# Psoc-robot.net
KiCad netlist of a schematic drawn in Altium Designer
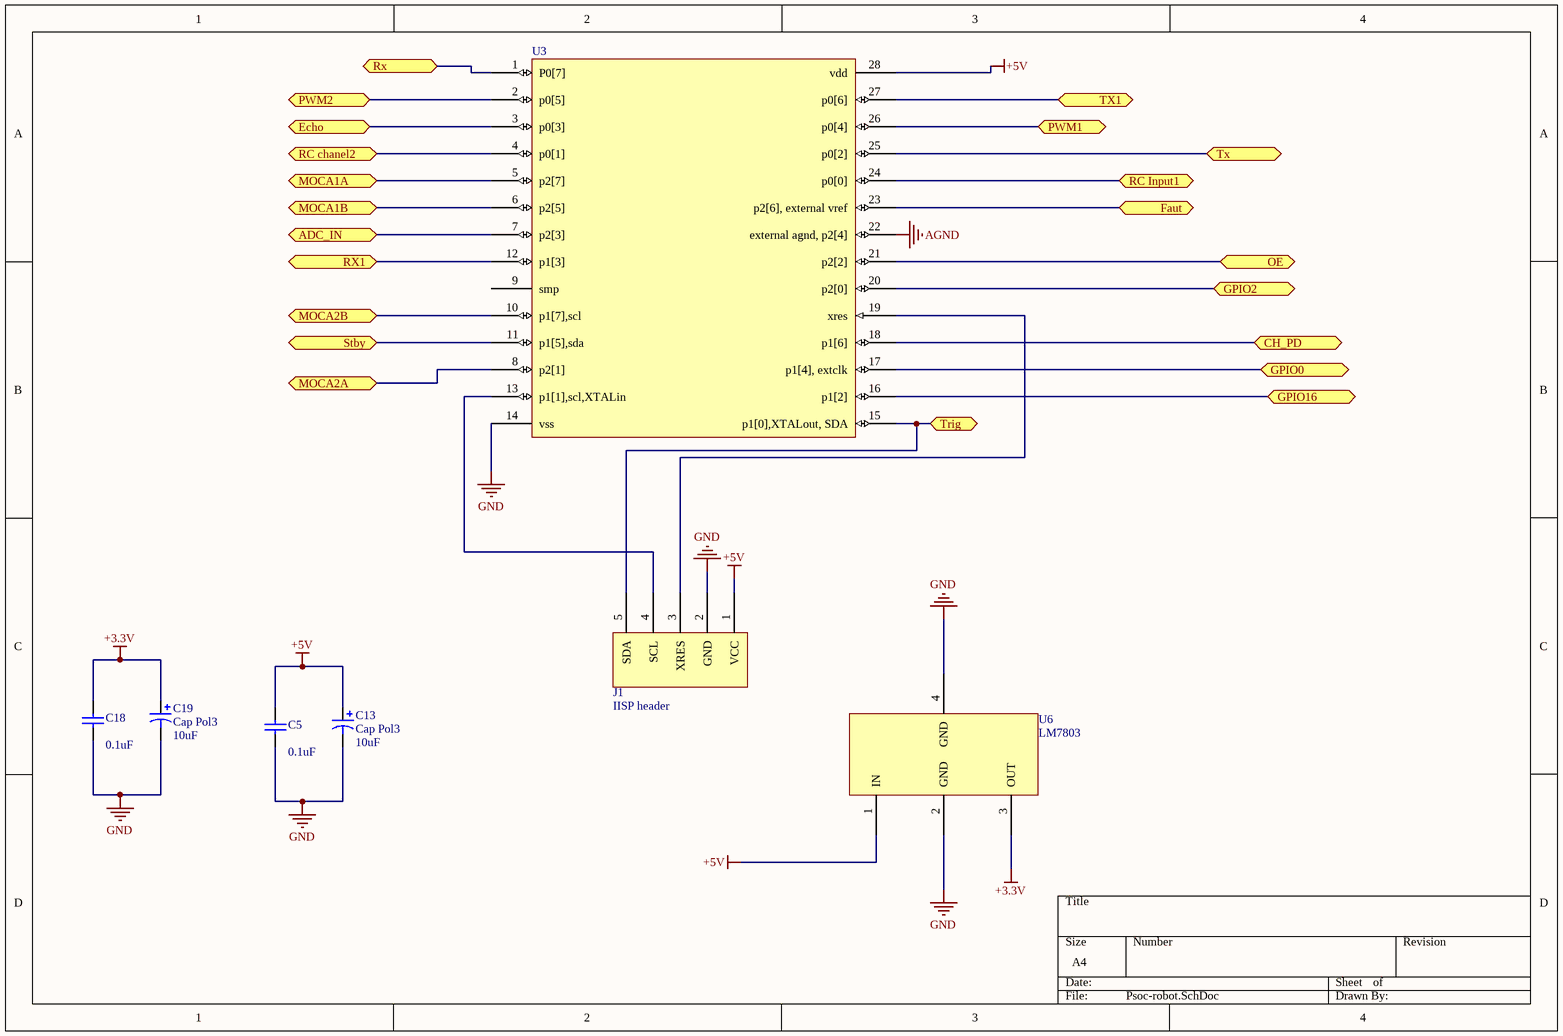
[diagram p0: Psoc-robot.SchDoc]

(export (version "E")
  (design (tool "Eeschema 10.0.6"))
  (components
    (comp (ref "C5")
      (value "0.1uF")
      (footprint "C1206")
      (description "Capacitor (Semiconductor SIM Model)")
      (fields (field (name "Comment") "Cap Semi") (field (name "PUBLISHER") "Altium Limited"))
      (libsource (lib "Miscellaneous Devices") (part "Cap Semi"))
    )
    (comp (ref "C13")
      (value "Cap Pol3")
      (footprint "C0805")
      (description "Polarized Capacitor (Surface Mount)")
      (fields (field (name "ALTIUM_VALUE") "10uF") (field (name "PUBLISHER") "Altium Limited"))
      (libsource (lib "Miscellaneous Devices") (part "Cap Pol3"))
    )
    (comp (ref "C18")
      (value "0.1uF")
      (footprint "C1206")
      (description "Capacitor (Semiconductor SIM Model)")
      (fields (field (name "Comment") "Cap Semi") (field (name "PUBLISHER") "Altium Limited"))
      (libsource (lib "Miscellaneous Devices") (part "Cap Semi"))
    )
    (comp (ref "C19")
      (value "Cap Pol3")
      (footprint "C0805")
      (description "Polarized Capacitor (Surface Mount)")
      (fields (field (name "ALTIUM_VALUE") "10uF") (field (name "PUBLISHER") "Altium Limited"))
      (libsource (lib "Miscellaneous Devices") (part "Cap Pol3"))
    )
    (comp (ref "J1")
      (value "IISP header")
      (footprint "Programm header")
      (libsource (lib "IISP_Header") (part "IISP header"))
    )
    (comp (ref "U3")
      (value "Component_1")
      (footprint "CY8C29466")
      (libsource (lib "CY8C29466") (part "Component_1"))
    )
    (comp (ref "U6") (value "LM7803") (footprint "LM7805") (libsource (lib "LM7805") (part "LM7803")))
  )
  (nets
    (net (code "1") (name "+3.3V") (class "Default")
      (node (ref "C18") (pin "1") (pinfunction "1_1") (pintype "passive"))
      (node (ref "C19") (pin "1") (pinfunction "1_1") (pintype "passive"))
      (node (ref "U6") (pin "3") (pinfunction "OUT_3") (pintype "passive"))
    )
    (net (code "2") (name "+5V") (class "Default")
      (node (ref "C13") (pin "1") (pinfunction "1_1") (pintype "passive"))
      (node (ref "C5") (pin "1") (pinfunction "1_1") (pintype "passive"))
      (node (ref "J1") (pin "1") (pinfunction "VCC_1") (pintype "passive"))
      (node (ref "U3") (pin "28") (pinfunction "vdd_28") (pintype "power_in"))
      (node (ref "U6") (pin "1") (pinfunction "IN_1") (pintype "passive"))
    )
    (net (code "3") (name "/ADC_IN") (class "Default")
      (node (ref "U3") (pin "7") (pinfunction "p2[3]_7") (pintype "bidirectional"))
    )
    (net (code "4") (name "/CH_PD") (class "Default")
      (node (ref "U3") (pin "18") (pinfunction "p1[6]_18") (pintype "bidirectional"))
    )
    (net (code "5") (name "/Echo") (class "Default")
      (node (ref "U3") (pin "3") (pinfunction "p0[3]_3") (pintype "bidirectional"))
    )
    (net (code "6") (name "/Faut") (class "Default")
      (node (ref "U3") (pin "23") (pinfunction "p2[6],_external_vref_23") (pintype "bidirectional"))
    )
    (net (code "7") (name "/GPIO0") (class "Default")
      (node (ref "U3") (pin "17") (pinfunction "p1[4],_extclk_17") (pintype "bidirectional"))
    )
    (net (code "8") (name "/GPIO2") (class "Default")
      (node (ref "U3") (pin "20") (pinfunction "p2[0]_20") (pintype "bidirectional"))
    )
    (net (code "9") (name "/GPIO16") (class "Default")
      (node (ref "U3") (pin "16") (pinfunction "p1[2]_16") (pintype "bidirectional"))
    )
    (net (code "10") (name "/MOCA1A") (class "Default")
      (node (ref "U3") (pin "5") (pinfunction "p2[7]_5") (pintype "bidirectional"))
    )
    (net (code "11") (name "/MOCA1B") (class "Default")
      (node (ref "U3") (pin "6") (pinfunction "p2[5]_6") (pintype "bidirectional"))
    )
    (net (code "12") (name "/MOCA2A") (class "Default")
      (node (ref "U3") (pin "8") (pinfunction "p2[1]_8") (pintype "bidirectional"))
    )
    (net (code "13") (name "/MOCA2B") (class "Default")
      (node (ref "U3") (pin "10") (pinfunction "p1[7],scl_10") (pintype "bidirectional"))
    )
    (net (code "14") (name "/OE") (class "Default")
      (node (ref "U3") (pin "21") (pinfunction "p2[2]_21") (pintype "bidirectional"))
    )
    (net (code "15") (name "/PWM1") (class "Default")
      (node (ref "U3") (pin "26") (pinfunction "p0[4]_26") (pintype "bidirectional"))
    )
    (net (code "16") (name "/PWM2") (class "Default")
      (node (ref "U3") (pin "2") (pinfunction "p0[5]_2") (pintype "bidirectional"))
    )
    (net (code "17") (name "/RC Input1") (class "Default")
      (node (ref "U3") (pin "24") (pinfunction "p0[0]_24") (pintype "bidirectional"))
    )
    (net (code "18") (name "/RC chanel2") (class "Default")
      (node (ref "U3") (pin "4") (pinfunction "p0[1]_4") (pintype "bidirectional"))
    )
    (net (code "19") (name "/RX1") (class "Default")
      (node (ref "U3") (pin "12") (pinfunction "p1[3]_12") (pintype "bidirectional"))
    )
    (net (code "20") (name "/Rx") (class "Default")
      (node (ref "U3") (pin "1") (pinfunction "P0[7]_1") (pintype "bidirectional"))
    )
    (net (code "21") (name "/Stby") (class "Default")
      (node (ref "U3") (pin "11") (pinfunction "p1[5],sda_11") (pintype "bidirectional"))
    )
    (net (code "22") (name "/TX1") (class "Default")
      (node (ref "U3") (pin "27") (pinfunction "p0[6]_27") (pintype "bidirectional"))
    )
    (net (code "23") (name "/Trig") (class "Default")
      (node (ref "J1") (pin "5") (pinfunction "SDA_5") (pintype "passive"))
      (node (ref "U3") (pin "15") (pinfunction "p1[0],XTALout,_SDA_15") (pintype "bidirectional"))
    )
    (net (code "24") (name "/Tx") (class "Default")
      (node (ref "U3") (pin "25") (pinfunction "p0[2]_25") (pintype "bidirectional"))
    )
    (net (code "25") (name "AGND") (class "Default")
      (node (ref "U3") (pin "22") (pinfunction "external_agnd,_p2[4]_22") (pintype "bidirectional"))
    )
    (net (code "26") (name "GND") (class "Default")
      (node (ref "C13") (pin "2") (pinfunction "2_2") (pintype "passive"))
      (node (ref "C18") (pin "2") (pinfunction "2_2") (pintype "passive"))
      (node (ref "C19") (pin "2") (pinfunction "2_2") (pintype "passive"))
      (node (ref "C5") (pin "2") (pinfunction "2_2") (pintype "passive"))
      (node (ref "J1") (pin "2") (pinfunction "GND_2") (pintype "passive"))
      (node (ref "U3") (pin "14") (pinfunction "vss_14") (pintype "power_in"))
      (node (ref "U6") (pin "2") (pinfunction "GND_2") (pintype "passive"))
      (node (ref "U6") (pin "4") (pinfunction "GND_4") (pintype "passive"))
    )
    (net (code "27") (name "Net-(J1-SCL)") (class "Default")
      (node (ref "J1") (pin "4") (pinfunction "SCL_4") (pintype "passive"))
      (node (ref "U3") (pin "13") (pinfunction "p1[1],scl,XTALin_13") (pintype "bidirectional"))
    )
    (net (code "28") (name "Net-(J1-XRES)") (class "Default")
      (node (ref "J1") (pin "3") (pinfunction "XRES_3") (pintype "passive"))
      (node (ref "U3") (pin "19") (pinfunction "xres_19") (pintype "input"))
    )
    (net (code "29") (name "unconnected-(U3-smp-Pad9)") (class "Default")
      (node (ref "U3") (pin "9") (pinfunction "smp_9") (pintype "power_in"))
    )
  )
)
